# 2015_Amother.net
KiCad netlist of a schematic drawn in EAGLE
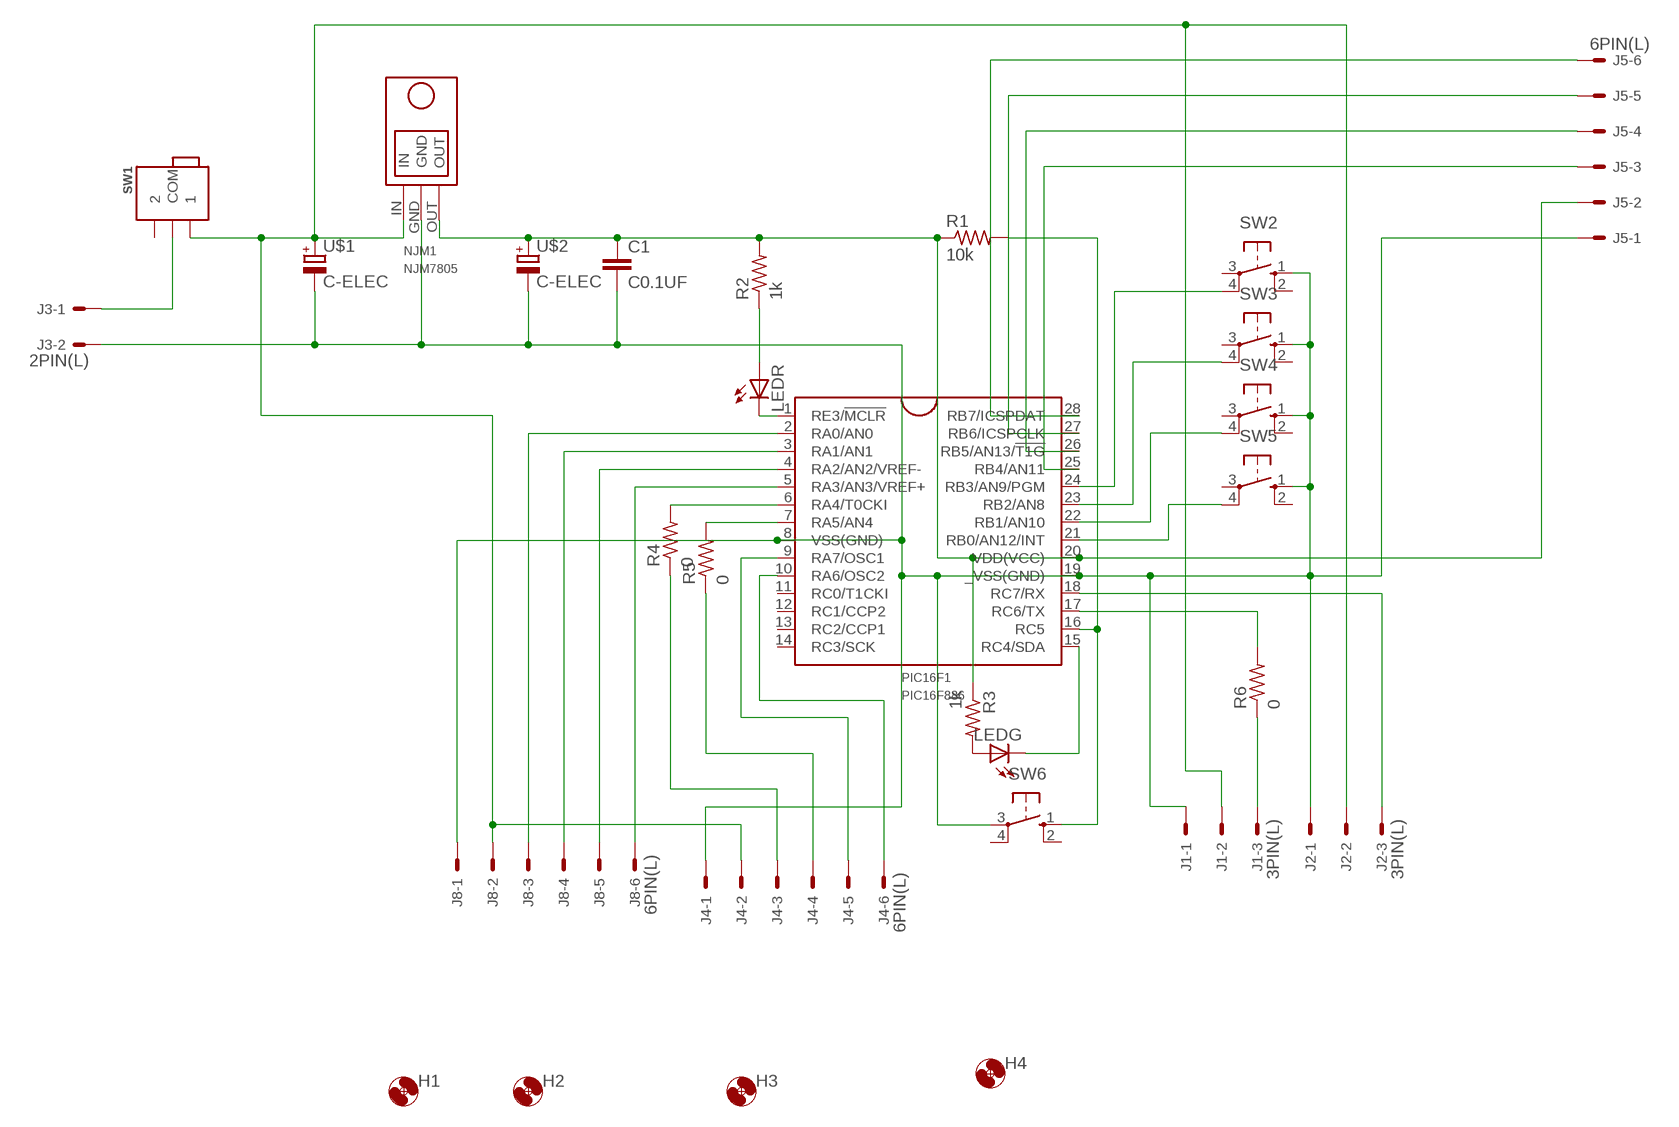
[diagram p0: schematic, sheet 1]

(export (version "E")
  (design (tool "Eeschema 10.0.6"))
  (components
    (comp (ref "C1")
      (value "C0.1UF")
      (footprint "eagle-import:C0.1UF")
      (libsource (lib "eagle-import") (part "C0.1UF"))
    )
    (comp (ref "H1")
      (value "HOLE3.3M3BOLT")
      (footprint "eagle-import:HOLE3.3")
      (libsource (lib "eagle-import") (part "HOLE3.3M3BOLT"))
    )
    (comp (ref "H2")
      (value "HOLE3.3M3BOLT")
      (footprint "eagle-import:HOLE3.3")
      (libsource (lib "eagle-import") (part "HOLE3.3M3BOLT"))
    )
    (comp (ref "H3")
      (value "HOLE3.3M3BOLT")
      (footprint "eagle-import:HOLE3.3")
      (libsource (lib "eagle-import") (part "HOLE3.3M3BOLT"))
    )
    (comp (ref "H4")
      (value "HOLE3.3M3BOLT")
      (footprint "eagle-import:HOLE3.3")
      (libsource (lib "eagle-import") (part "HOLE3.3M3BOLT"))
    )
    (comp (ref "J1")
      (value "3PIN(L)")
      (footprint "eagle-import:3PL")
      (libsource (lib "eagle-import") (part "3PIN(L)"))
    )
    (comp (ref "J2")
      (value "3PIN(L)")
      (footprint "eagle-import:3PL")
      (libsource (lib "eagle-import") (part "3PIN(L)"))
    )
    (comp (ref "J3")
      (value "2PIN(L)")
      (footprint "eagle-import:2PL")
      (libsource (lib "eagle-import") (part "2PIN(L)"))
    )
    (comp (ref "J4")
      (value "6PIN(L)")
      (footprint "eagle-import:6PL")
      (libsource (lib "eagle-import") (part "6PIN(L)"))
    )
    (comp (ref "J5")
      (value "6PIN(L)")
      (footprint "eagle-import:6PL")
      (libsource (lib "eagle-import") (part "6PIN(L)"))
    )
    (comp (ref "J8")
      (value "6PIN(L)")
      (footprint "eagle-import:6PL")
      (libsource (lib "eagle-import") (part "6PIN(L)"))
    )
    (comp (ref "LEDG")
      (value "LED3MM")
      (footprint "eagle-import:LED3MM")
      (libsource (lib "eagle-import") (part "LED3MM"))
    )
    (comp (ref "LEDR")
      (value "LED3MM")
      (footprint "eagle-import:LED3MM")
      (libsource (lib "eagle-import") (part "LED3MM"))
    )
    (comp (ref "NJM1")
      (value "NJM7805")
      (footprint "eagle-import:NJM7805")
      (libsource (lib "eagle-import") (part "NJM7805"))
    )
    (comp (ref "PIC16F1")
      (value "PIC16F886")
      (footprint "eagle-import:DIL28-3")
      (libsource (lib "eagle-import") (part "PIC16F886"))
    )
    (comp (ref "R1")
      (value "10k")
      (footprint "eagle-import:0207_10")
      (libsource (lib "eagle-import") (part "R-"))
    )
    (comp (ref "R2")
      (value "1k")
      (footprint "eagle-import:0207_10")
      (libsource (lib "eagle-import") (part "R-"))
    )
    (comp (ref "R3")
      (value "1k")
      (footprint "eagle-import:0207_10")
      (libsource (lib "eagle-import") (part "R-"))
    )
    (comp (ref "R4")
      (value "0")
      (footprint "eagle-import:0207_10")
      (libsource (lib "eagle-import") (part "R-"))
    )
    (comp (ref "R5")
      (value "0")
      (footprint "eagle-import:0207_10")
      (libsource (lib "eagle-import") (part "R-"))
    )
    (comp (ref "R6")
      (value "0")
      (footprint "eagle-import:0207_10")
      (libsource (lib "eagle-import") (part "R-"))
    )
    (comp (ref "SW1")
      (value "SWITCH_MININORMAL")
      (footprint "eagle-import:SWITCH_MINI")
      (libsource (lib "eagle-import") (part "SWITCH_MININORMAL"))
    )
    (comp (ref "SW2")
      (value "TACTSW")
      (footprint "eagle-import:TACT")
      (libsource (lib "eagle-import") (part "TACTSW"))
    )
    (comp (ref "SW3")
      (value "TACTSW")
      (footprint "eagle-import:TACT")
      (libsource (lib "eagle-import") (part "TACTSW"))
    )
    (comp (ref "SW4")
      (value "TACTSW")
      (footprint "eagle-import:TACT")
      (libsource (lib "eagle-import") (part "TACTSW"))
    )
    (comp (ref "SW5")
      (value "TACTSW")
      (footprint "eagle-import:TACT")
      (libsource (lib "eagle-import") (part "TACTSW"))
    )
    (comp (ref "SW6")
      (value "TACTSW")
      (footprint "eagle-import:TACT")
      (libsource (lib "eagle-import") (part "TACTSW"))
    )
    (comp (ref "U$1")
      (value "C-ELEC")
      (footprint "eagle-import:C-6MM")
      (libsource (lib "eagle-import") (part "C-ELEC"))
    )
    (comp (ref "U$2")
      (value "C-ELEC")
      (footprint "eagle-import:C-6MM")
      (libsource (lib "eagle-import") (part "C-ELEC"))
    )
  )
  (nets
    (net (code "1") (name "Net-(J1A-S)") (class "Default")
      (node (ref "C1") (pin "2") (pinfunction "2_2") (pintype "passive"))
      (node (ref "J1") (pin "1") (pinfunction "S_1") (pintype "passive"))
      (node (ref "J2") (pin "1") (pinfunction "S_1") (pintype "passive"))
      (node (ref "J3") (pin "2") (pinfunction "S_2") (pintype "passive"))
      (node (ref "J4") (pin "1") (pinfunction "S_1") (pintype "passive"))
      (node (ref "J5") (pin "1") (pinfunction "S_1") (pintype "passive"))
      (node (ref "J8") (pin "1") (pinfunction "S_1") (pintype "passive"))
      (node (ref "NJM1") (pin "GND") (pinfunction "GND_GND") (pintype "bidirectional"))
      (node (ref "PIC16F1") (pin "19") (pinfunction "_VSS(GND)_19") (pintype "power_in"))
      (node (ref "PIC16F1") (pin "8") (pinfunction "VSS(GND)_8") (pintype "power_in"))
      (node (ref "SW2") (pin "1") (pinfunction "S_1") (pintype "passive"))
      (node (ref "SW3") (pin "1") (pinfunction "S_1") (pintype "passive"))
      (node (ref "SW4") (pin "1") (pinfunction "S_1") (pintype "passive"))
      (node (ref "SW5") (pin "1") (pinfunction "S_1") (pintype "passive"))
      (node (ref "SW6") (pin "3") (pinfunction "P_3") (pintype "passive"))
      (node (ref "U$1") (pin "-") (pinfunction "-_-") (pintype "passive"))
      (node (ref "U$2") (pin "-") (pinfunction "-_-") (pintype "passive"))
    )
    (net (code "2") (name "Net-(J1B-S)") (class "Default")
      (node (ref "J1") (pin "2") (pinfunction "S_2") (pintype "passive"))
      (node (ref "J2") (pin "2") (pinfunction "S_2") (pintype "passive"))
      (node (ref "J4") (pin "2") (pinfunction "S_2") (pintype "passive"))
      (node (ref "J8") (pin "2") (pinfunction "S_2") (pintype "passive"))
      (node (ref "NJM1") (pin "IN") (pinfunction "IN_IN") (pintype "bidirectional"))
      (node (ref "SW1") (pin "1") (pinfunction "1_1") (pintype "passive"))
      (node (ref "U$1") (pin "+") (pinfunction "+_+") (pintype "passive"))
    )
    (net (code "3") (name "Net-(J1C-S)") (class "Default")
      (node (ref "J1") (pin "3") (pinfunction "S_3") (pintype "passive"))
      (node (ref "R6") (pin "1") (pinfunction "1_1") (pintype "passive"))
    )
    (net (code "4") (name "Net-(J2C-S)") (class "Default")
      (node (ref "J2") (pin "3") (pinfunction "S_3") (pintype "passive"))
      (node (ref "PIC16F1") (pin "18") (pinfunction "RC7/RX_18") (pintype "bidirectional"))
    )
    (net (code "5") (name "Net-(J3A-S)") (class "Default")
      (node (ref "J3") (pin "1") (pinfunction "S_1") (pintype "passive"))
      (node (ref "SW1") (pin "COM") (pinfunction "COM_COM") (pintype "passive"))
    )
    (net (code "6") (name "Net-(J4C-S)") (class "Default")
      (node (ref "J4") (pin "3") (pinfunction "S_3") (pintype "passive"))
      (node (ref "R4") (pin "1") (pinfunction "1_1") (pintype "passive"))
    )
    (net (code "7") (name "Net-(J4D-S)") (class "Default")
      (node (ref "J4") (pin "4") (pinfunction "S_4") (pintype "passive"))
      (node (ref "R5") (pin "1") (pinfunction "1_1") (pintype "passive"))
    )
    (net (code "8") (name "Net-(J4E-S)") (class "Default")
      (node (ref "J4") (pin "5") (pinfunction "S_5") (pintype "passive"))
      (node (ref "PIC16F1") (pin "9") (pinfunction "RA7/OSC1_9") (pintype "bidirectional"))
    )
    (net (code "9") (name "Net-(J4F-S)") (class "Default")
      (node (ref "J4") (pin "6") (pinfunction "S_6") (pintype "passive"))
      (node (ref "PIC16F1") (pin "10") (pinfunction "RA6/OSC2_10") (pintype "bidirectional"))
    )
    (net (code "10") (name "Net-(J5B-S)") (class "Default")
      (node (ref "C1") (pin "1") (pinfunction "1_1") (pintype "passive"))
      (node (ref "J5") (pin "2") (pinfunction "S_2") (pintype "passive"))
      (node (ref "NJM1") (pin "OUT") (pinfunction "OUT_OUT") (pintype "bidirectional"))
      (node (ref "PIC16F1") (pin "20") (pinfunction "VDD(VCC)_20") (pintype "power_in"))
      (node (ref "R1") (pin "1") (pinfunction "1_1") (pintype "passive"))
      (node (ref "R2") (pin "2") (pinfunction "2_2") (pintype "passive"))
      (node (ref "R3") (pin "1") (pinfunction "1_1") (pintype "passive"))
      (node (ref "U$2") (pin "+") (pinfunction "+_+") (pintype "passive"))
    )
    (net (code "11") (name "Net-(J5C-S)") (class "Default")
      (node (ref "J5") (pin "3") (pinfunction "S_3") (pintype "passive"))
      (node (ref "PIC16F1") (pin "25") (pinfunction "RB4/AN11_25") (pintype "bidirectional"))
    )
    (net (code "12") (name "Net-(J5D-S)") (class "Default")
      (node (ref "J5") (pin "4") (pinfunction "S_4") (pintype "passive"))
      (node (ref "PIC16F1") (pin "26") (pinfunction "RB5/AN13/~{T1G}_26") (pintype "bidirectional"))
    )
    (net (code "13") (name "Net-(J5E-S)") (class "Default")
      (node (ref "J5") (pin "5") (pinfunction "S_5") (pintype "passive"))
      (node (ref "PIC16F1") (pin "27") (pinfunction "RB6/ICSPCLK_27") (pintype "bidirectional"))
    )
    (net (code "14") (name "Net-(J5F-S)") (class "Default")
      (node (ref "J5") (pin "6") (pinfunction "S_6") (pintype "passive"))
      (node (ref "PIC16F1") (pin "28") (pinfunction "RB7/ICSPDAT_28") (pintype "bidirectional"))
    )
    (net (code "15") (name "Net-(J8C-S)") (class "Default")
      (node (ref "J8") (pin "3") (pinfunction "S_3") (pintype "passive"))
      (node (ref "PIC16F1") (pin "2") (pinfunction "RA0/AN0_2") (pintype "bidirectional"))
    )
    (net (code "16") (name "Net-(J8D-S)") (class "Default")
      (node (ref "J8") (pin "4") (pinfunction "S_4") (pintype "passive"))
      (node (ref "PIC16F1") (pin "3") (pinfunction "RA1/AN1_3") (pintype "bidirectional"))
    )
    (net (code "17") (name "Net-(J8E-S)") (class "Default")
      (node (ref "J8") (pin "5") (pinfunction "S_5") (pintype "passive"))
      (node (ref "PIC16F1") (pin "4") (pinfunction "RA2/AN2/VREF-_4") (pintype "bidirectional"))
    )
    (net (code "18") (name "Net-(J8F-S)") (class "Default")
      (node (ref "J8") (pin "6") (pinfunction "S_6") (pintype "passive"))
      (node (ref "PIC16F1") (pin "5") (pinfunction "RA3/AN3/VREF+_5") (pintype "bidirectional"))
    )
    (net (code "19") (name "Net-(LEDG-C)") (class "Default")
      (node (ref "LEDG") (pin "K") (pinfunction "C_K") (pintype "passive"))
      (node (ref "PIC16F1") (pin "15") (pinfunction "RC4/SDA_15") (pintype "bidirectional"))
    )
    (net (code "20") (name "Net-(LEDG-PadA)") (class "Default")
      (node (ref "LEDG") (pin "A") (pinfunction "A_A") (pintype "passive"))
      (node (ref "R3") (pin "2") (pinfunction "2_2") (pintype "passive"))
    )
    (net (code "21") (name "Net-(LEDR-C)") (class "Default")
      (node (ref "LEDR") (pin "K") (pinfunction "C_K") (pintype "passive"))
      (node (ref "PIC16F1") (pin "1") (pinfunction "RE3/~{MCLR}_1") (pintype "bidirectional"))
    )
    (net (code "22") (name "Net-(LEDR-PadA)") (class "Default")
      (node (ref "LEDR") (pin "A") (pinfunction "A_A") (pintype "passive"))
      (node (ref "R2") (pin "1") (pinfunction "1_1") (pintype "passive"))
    )
    (net (code "23") (name "Net-(PIC16F1-RA4{slash}T0CKI)") (class "Default")
      (node (ref "PIC16F1") (pin "6") (pinfunction "RA4/T0CKI_6") (pintype "bidirectional"))
      (node (ref "R4") (pin "2") (pinfunction "2_2") (pintype "passive"))
    )
    (net (code "24") (name "Net-(PIC16F1-RA5{slash}AN4)") (class "Default")
      (node (ref "PIC16F1") (pin "7") (pinfunction "RA5/AN4_7") (pintype "bidirectional"))
      (node (ref "R5") (pin "2") (pinfunction "2_2") (pintype "passive"))
    )
    (net (code "25") (name "Net-(PIC16F1-RB0{slash}AN12{slash}INT)") (class "Default")
      (node (ref "PIC16F1") (pin "21") (pinfunction "RB0/AN12/INT_21") (pintype "bidirectional"))
      (node (ref "SW5") (pin "4") (pinfunction "P1_4") (pintype "passive"))
    )
    (net (code "26") (name "Net-(PIC16F1-RB1{slash}AN10)") (class "Default")
      (node (ref "PIC16F1") (pin "22") (pinfunction "RB1/AN10_22") (pintype "bidirectional"))
      (node (ref "SW4") (pin "4") (pinfunction "P1_4") (pintype "passive"))
    )
    (net (code "27") (name "Net-(PIC16F1-RB2{slash}AN8)") (class "Default")
      (node (ref "PIC16F1") (pin "23") (pinfunction "RB2/AN8_23") (pintype "bidirectional"))
      (node (ref "SW3") (pin "4") (pinfunction "P1_4") (pintype "passive"))
    )
    (net (code "28") (name "Net-(PIC16F1-RB3{slash}AN9{slash}PGM)") (class "Default")
      (node (ref "PIC16F1") (pin "24") (pinfunction "RB3/AN9/PGM_24") (pintype "bidirectional"))
      (node (ref "SW2") (pin "4") (pinfunction "P1_4") (pintype "passive"))
    )
    (net (code "29") (name "Net-(PIC16F1-RC5)") (class "Default")
      (node (ref "PIC16F1") (pin "16") (pinfunction "RC5_16") (pintype "bidirectional"))
      (node (ref "R1") (pin "2") (pinfunction "2_2") (pintype "passive"))
      (node (ref "SW6") (pin "1") (pinfunction "S_1") (pintype "passive"))
    )
    (net (code "30") (name "Net-(PIC16F1-RC6{slash}TX)") (class "Default")
      (node (ref "PIC16F1") (pin "17") (pinfunction "RC6/TX_17") (pintype "bidirectional"))
      (node (ref "R6") (pin "2") (pinfunction "2_2") (pintype "passive"))
    )
    (net (code "31") (name "unconnected-(PIC16F1-RC0{slash}T1CKI-Pad11)") (class "Default")
      (node (ref "PIC16F1") (pin "11") (pinfunction "RC0/T1CKI_11") (pintype "bidirectional"))
    )
    (net (code "32") (name "unconnected-(PIC16F1-RC1{slash}CCP2-Pad12)") (class "Default")
      (node (ref "PIC16F1") (pin "12") (pinfunction "RC1/CCP2_12") (pintype "bidirectional"))
    )
    (net (code "33") (name "unconnected-(PIC16F1-RC2{slash}CCP1-Pad13)") (class "Default")
      (node (ref "PIC16F1") (pin "13") (pinfunction "RC2/CCP1_13") (pintype "bidirectional"))
    )
    (net (code "34") (name "unconnected-(PIC16F1-RC3{slash}SCK-Pad14)") (class "Default")
      (node (ref "PIC16F1") (pin "14") (pinfunction "RC3/SCK_14") (pintype "bidirectional"))
    )
    (net (code "35") (name "unconnected-(SW1-Pad2)") (class "Default")
      (node (ref "SW1") (pin "2") (pinfunction "2_2") (pintype "no_connect"))
    )
    (net (code "36") (name "unconnected-(SW2-P-Pad3)") (class "Default")
      (node (ref "SW2") (pin "3") (pinfunction "P_3") (pintype "passive"))
    )
    (net (code "37") (name "unconnected-(SW2-S1-Pad2)") (class "Default")
      (node (ref "SW2") (pin "2") (pinfunction "S1_2") (pintype "passive"))
    )
    (net (code "38") (name "unconnected-(SW3-P-Pad3)") (class "Default")
      (node (ref "SW3") (pin "3") (pinfunction "P_3") (pintype "passive"))
    )
    (net (code "39") (name "unconnected-(SW3-S1-Pad2)") (class "Default")
      (node (ref "SW3") (pin "2") (pinfunction "S1_2") (pintype "passive"))
    )
    (net (code "40") (name "unconnected-(SW4-P-Pad3)") (class "Default")
      (node (ref "SW4") (pin "3") (pinfunction "P_3") (pintype "passive"))
    )
    (net (code "41") (name "unconnected-(SW4-S1-Pad2)") (class "Default")
      (node (ref "SW4") (pin "2") (pinfunction "S1_2") (pintype "passive"))
    )
    (net (code "42") (name "unconnected-(SW5-P-Pad3)") (class "Default")
      (node (ref "SW5") (pin "3") (pinfunction "P_3") (pintype "passive"))
    )
    (net (code "43") (name "unconnected-(SW5-S1-Pad2)") (class "Default")
      (node (ref "SW5") (pin "2") (pinfunction "S1_2") (pintype "passive"))
    )
    (net (code "44") (name "unconnected-(SW6-P1-Pad4)") (class "Default")
      (node (ref "SW6") (pin "4") (pinfunction "P1_4") (pintype "passive"))
    )
    (net (code "45") (name "unconnected-(SW6-S1-Pad2)") (class "Default")
      (node (ref "SW6") (pin "2") (pinfunction "S1_2") (pintype "passive"))
    )
  )
)
